# AC.net
KiCad netlist of a schematic drawn in EAGLE
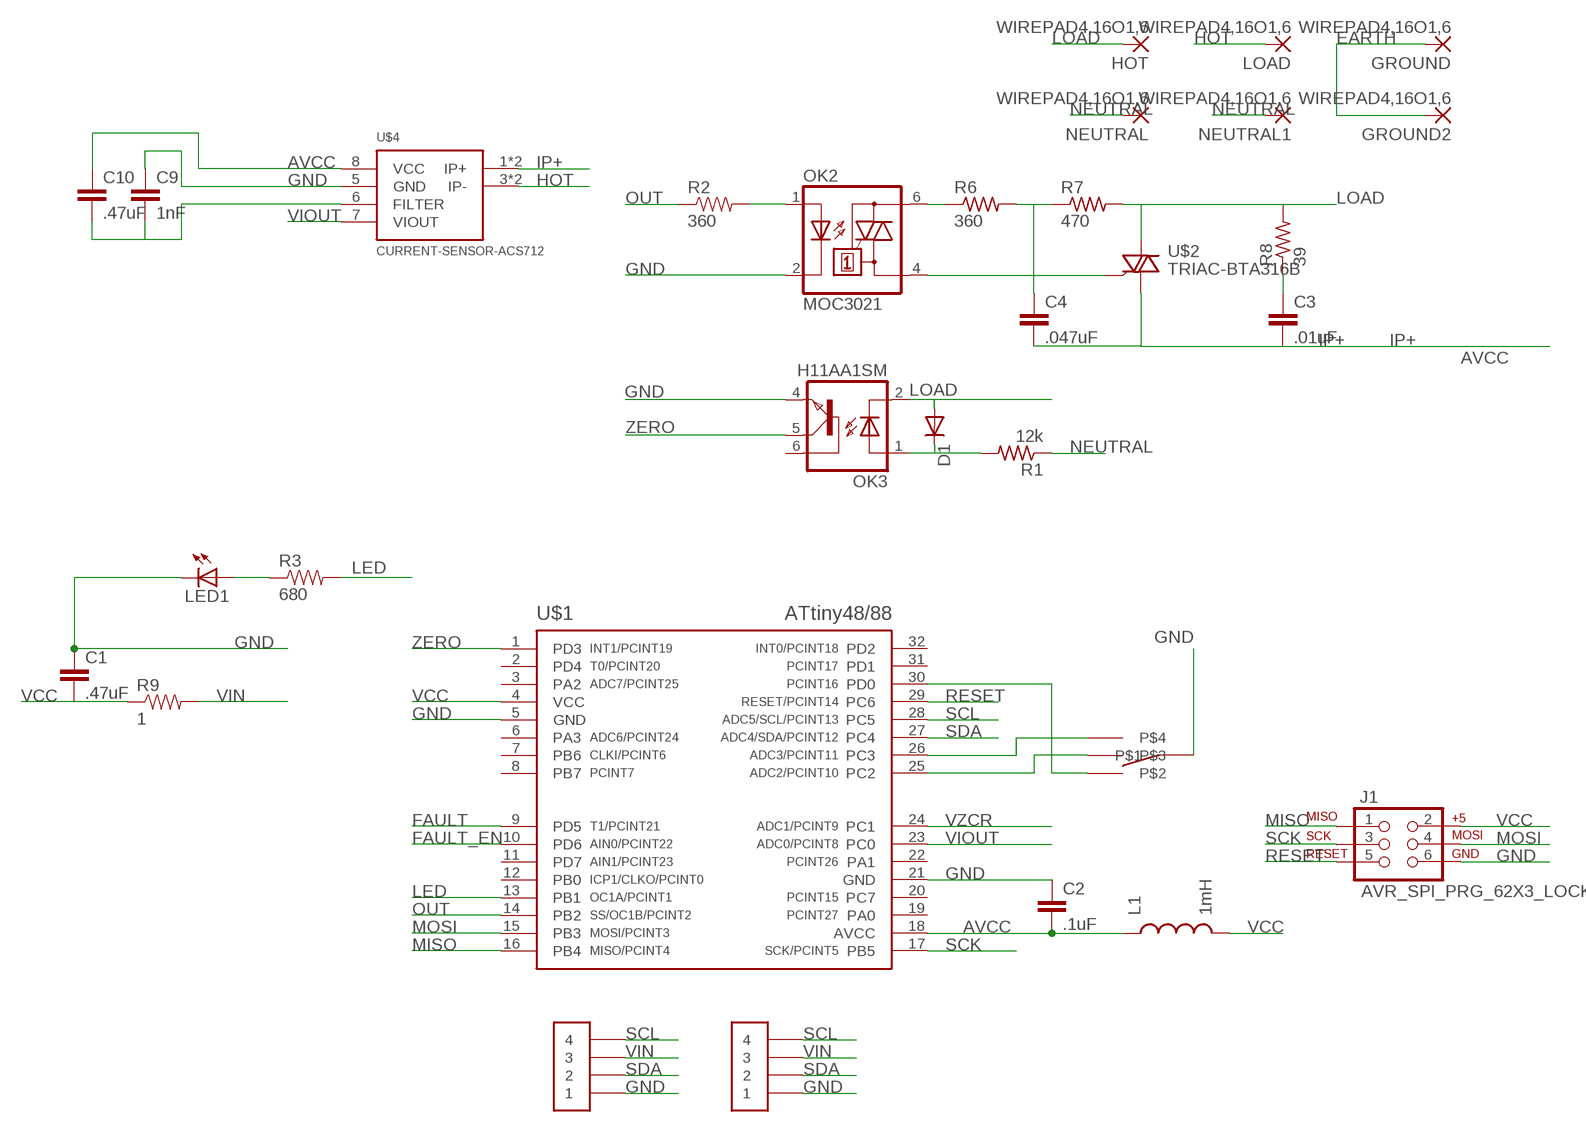
[diagram p0: schematic, sheet 1]

(export (version "E")
  (design (tool "Eeschema 10.0.6"))
  (components
    (comp (ref "C1")
      (value ".47uF")
      (footprint "eagle-import:0805")
      (libsource (lib "eagle-import") (part "CAP0805"))
    )
    (comp (ref "C2")
      (value ".1uF")
      (footprint "eagle-import:0805")
      (libsource (lib "eagle-import") (part "CAP0805"))
    )
    (comp (ref "C3")
      (value ".01uF")
      (footprint "eagle-import:C1206")
      (libsource (lib "eagle-import") (part "C-EUC1206"))
    )
    (comp (ref "C4")
      (value ".047uF")
      (footprint "eagle-import:C1206")
      (libsource (lib "eagle-import") (part "C-EUC1206"))
    )
    (comp (ref "C9")
      (value "1nF")
      (footprint "eagle-import:0805")
      (libsource (lib "eagle-import") (part "CAP0805"))
    )
    (comp (ref "C10")
      (value ".47uF")
      (footprint "eagle-import:0805")
      (libsource (lib "eagle-import") (part "CAP0805"))
    )
    (comp (ref "D1")
      (value "DIODESMA")
      (footprint "eagle-import:SMA-DIODE")
      (libsource (lib "eagle-import") (part "DIODESMA"))
    )
    (comp (ref "GROUND")
      (value "WIREPAD4,16O1,6")
      (footprint "eagle-import:4,16O1,6")
      (libsource (lib "eagle-import") (part "WIREPAD4,16O1,6"))
    )
    (comp (ref "GROUND2")
      (value "WIREPAD4,16O1,6")
      (footprint "eagle-import:4,16O1,6")
      (libsource (lib "eagle-import") (part "WIREPAD4,16O1,6"))
    )
    (comp (ref "HOT")
      (value "WIREPAD4,16O1,6")
      (footprint "eagle-import:4,16O1,6")
      (libsource (lib "eagle-import") (part "WIREPAD4,16O1,6"))
    )
    (comp (ref "J1")
      (value "AVR_SPI_PRG_62X3_LOCK")
      (footprint "eagle-import:2X3_LOCK")
      (libsource (lib "eagle-import") (part "AVR_SPI_PRG_62X3_LOCK"))
    )
    (comp (ref "JP1")
      (value "HEADER-1X4MOLEX-SL")
      (footprint "eagle-import:HEADER-1X4-MOLEX-SL")
      (libsource (lib "eagle-import") (part "HEADER-1X4MOLEX-SL"))
    )
    (comp (ref "JP2")
      (value "HEADER-1X4MOLEX-SL")
      (footprint "eagle-import:HEADER-1X4-MOLEX-SL")
      (libsource (lib "eagle-import") (part "HEADER-1X4MOLEX-SL"))
    )
    (comp (ref "L1")
      (value "1mH")
      (footprint "eagle-import:1007")
      (libsource (lib "eagle-import") (part "INDUCTOR1007"))
    )
    (comp (ref "LED1")
      (value "LED5MM")
      (footprint "eagle-import:LED5MM")
      (libsource (lib "eagle-import") (part "LED5MM"))
    )
    (comp (ref "LOAD")
      (value "WIREPAD4,16O1,6")
      (footprint "eagle-import:4,16O1,6")
      (libsource (lib "eagle-import") (part "WIREPAD4,16O1,6"))
    )
    (comp (ref "NEUTRAL")
      (value "WIREPAD4,16O1,6")
      (footprint "eagle-import:4,16O1,6")
      (libsource (lib "eagle-import") (part "WIREPAD4,16O1,6"))
    )
    (comp (ref "NEUTRAL1")
      (value "WIREPAD4,16O1,6")
      (footprint "eagle-import:4,16O1,6")
      (libsource (lib "eagle-import") (part "WIREPAD4,16O1,6"))
    )
    (comp (ref "OK2")
      (value "MOC3021")
      (footprint "eagle-import:DIL6-SMD")
      (fields (field (name "MF") "FAIRCHILD SEMICONDUCTOR") (field (name "MPN") "MOC3031SM"))
      (libsource (lib "eagle-import") (part "MOC30S31"))
    )
    (comp (ref "OK3")
      (value "H11AA1SM")
      (footprint "eagle-import:DIL6-SMD")
      (libsource (lib "eagle-import") (part "H11A?MS1"))
    )
    (comp (ref "R1")
      (value "12k")
      (footprint "eagle-import:R1206")
      (libsource (lib "eagle-import") (part "R-US_R1206"))
    )
    (comp (ref "R2")
      (value "360")
      (footprint "eagle-import:0805")
      (libsource (lib "eagle-import") (part "SparkFun-Resistors_RESISTOR0805-RES"))
    )
    (comp (ref "R3")
      (value "680")
      (footprint "eagle-import:0805")
      (libsource (lib "eagle-import") (part "RESISTOR0805-RES"))
    )
    (comp (ref "R6")
      (value "360")
      (footprint "eagle-import:R1206")
      (libsource (lib "eagle-import") (part "R-US_R1206"))
    )
    (comp (ref "R7")
      (value "470")
      (footprint "eagle-import:R1206")
      (libsource (lib "eagle-import") (part "R-US_R1206"))
    )
    (comp (ref "R8")
      (value "39")
      (footprint "eagle-import:R1206")
      (libsource (lib "eagle-import") (part "R-US_R1206"))
    )
    (comp (ref "R9")
      (value "1")
      (footprint "eagle-import:0805")
      (libsource (lib "eagle-import") (part "SparkFun-Resistors_RESISTOR0805-RES"))
    )
    (comp (ref "U$1")
      (value "ATTINY48/88-TQFP")
      (footprint "eagle-import:TQFP-32")
      (libsource (lib "eagle-import") (part "ATTINY48/88-TQFP"))
    )
    (comp (ref "U$2")
      (value "TRIAC-BTA316B")
      (footprint "eagle-import:D2PACK")
      (libsource (lib "eagle-import") (part "TRIAC-BTA316B"))
    )
    (comp (ref "U$3")
      (value "SWITCH-SP3T")
      (footprint "eagle-import:SWITCH-SLIDE-APEM-MHS133K")
      (libsource (lib "eagle-import") (part "SWITCH-SP3T"))
    )
    (comp (ref "U$4")
      (value "CURRENT-SENSOR-ACS712")
      (footprint "eagle-import:SOIC-8")
      (libsource (lib "eagle-import") (part "CURRENT-SENSOR-ACS712"))
    )
  )
  (nets
    (net (code "1") (name "/AVCC") (class "Default")
      (node (ref "C10") (pin "1") (pinfunction "1_1") (pintype "passive"))
      (node (ref "C2") (pin "2") (pinfunction "2_2") (pintype "passive"))
      (node (ref "L1") (pin "1") (pinfunction "1_1") (pintype "passive"))
      (node (ref "U$1") (pin "18") (pinfunction "AVCC_18") (pintype "power_in"))
      (node (ref "U$4") (pin "8") (pinfunction "VCC_8") (pintype "bidirectional"))
    )
    (net (code "2") (name "/EARTH") (class "Default")
      (node (ref "GROUND") (pin "1") (pinfunction "P_1") (pintype "passive"))
      (node (ref "GROUND2") (pin "1") (pinfunction "P_1") (pintype "passive"))
    )
    (net (code "3") (name "/FAULT") (class "Default")
      (node (ref "U$1") (pin "9") (pinfunction "PD5_9") (pintype "bidirectional"))
    )
    (net (code "4") (name "/FAULT_EN") (class "Default")
      (node (ref "U$1") (pin "10") (pinfunction "PD6_10") (pintype "bidirectional"))
    )
    (net (code "5") (name "/GND") (class "Default")
      (node (ref "C1") (pin "1") (pinfunction "1_1") (pintype "passive"))
      (node (ref "C2") (pin "1") (pinfunction "1_1") (pintype "passive"))
      (node (ref "C9") (pin "1") (pinfunction "1_1") (pintype "passive"))
      (node (ref "J1") (pin "6") (pinfunction "6_6") (pintype "passive"))
      (node (ref "JP1") (pin "P$1") (pinfunction "1_P$1") (pintype "bidirectional"))
      (node (ref "JP2") (pin "P$1") (pinfunction "1_P$1") (pintype "bidirectional"))
      (node (ref "LED1") (pin "K") (pinfunction "C_K") (pintype "passive"))
      (node (ref "OK2") (pin "2") (pinfunction "C_2") (pintype "passive"))
      (node (ref "OK3") (pin "4") (pinfunction "EMI_4") (pintype "passive"))
      (node (ref "U$1") (pin "21") (pinfunction "GND_21") (pintype "bidirectional"))
      (node (ref "U$1") (pin "5") (pinfunction "GND_5") (pintype "bidirectional"))
      (node (ref "U$3") (pin "P2") (pinfunction "P$1_P2") (pintype "bidirectional"))
      (node (ref "U$4") (pin "5") (pinfunction "GND_5") (pintype "bidirectional"))
    )
    (net (code "6") (name "/HOT") (class "Default")
      (node (ref "LOAD") (pin "1") (pinfunction "P_1") (pintype "passive"))
      (node (ref "U$4") (pin "3") (pinfunction "IP-_3") (pintype "bidirectional"))
      (node (ref "U$4") (pin "4") (pinfunction "IP-_4") (pintype "bidirectional"))
    )
    (net (code "7") (name "/IP+") (class "Default")
      (node (ref "C3") (pin "2") (pinfunction "2_2") (pintype "passive"))
      (node (ref "C4") (pin "2") (pinfunction "2_2") (pintype "passive"))
      (node (ref "U$2") (pin "1") (pinfunction "A1_1") (pintype "passive"))
      (node (ref "U$4") (pin "1") (pinfunction "IP+_1") (pintype "bidirectional"))
      (node (ref "U$4") (pin "2") (pinfunction "IP+_2") (pintype "bidirectional"))
    )
    (net (code "8") (name "/LED") (class "Default")
      (node (ref "R3") (pin "2") (pinfunction "2_2") (pintype "passive"))
      (node (ref "U$1") (pin "13") (pinfunction "PB1_13") (pintype "bidirectional"))
    )
    (net (code "9") (name "/LOAD") (class "Default")
      (node (ref "D1") (pin "A") (pinfunction "A_A") (pintype "passive"))
      (node (ref "HOT") (pin "1") (pinfunction "P_1") (pintype "passive"))
      (node (ref "OK3") (pin "2") (pinfunction "C_2") (pintype "passive"))
      (node (ref "R7") (pin "2") (pinfunction "2_2") (pintype "passive"))
      (node (ref "R8") (pin "2") (pinfunction "2_2") (pintype "passive"))
      (node (ref "U$2") (pin "2") (pinfunction "A2_2") (pintype "passive"))
    )
    (net (code "10") (name "/MISO") (class "Default")
      (node (ref "J1") (pin "1") (pinfunction "1_1") (pintype "passive"))
      (node (ref "U$1") (pin "16") (pinfunction "PB4_16") (pintype "bidirectional"))
    )
    (net (code "11") (name "/MOSI") (class "Default")
      (node (ref "J1") (pin "4") (pinfunction "4_4") (pintype "passive"))
      (node (ref "U$1") (pin "15") (pinfunction "PB3_15") (pintype "bidirectional"))
    )
    (net (code "12") (name "/NEUTRAL") (class "Default")
      (node (ref "NEUTRAL") (pin "1") (pinfunction "P_1") (pintype "passive"))
      (node (ref "NEUTRAL1") (pin "1") (pinfunction "P_1") (pintype "passive"))
      (node (ref "R1") (pin "1") (pinfunction "1_1") (pintype "passive"))
    )
    (net (code "13") (name "/OUT") (class "Default")
      (node (ref "R2") (pin "1") (pinfunction "1_1") (pintype "passive"))
      (node (ref "U$1") (pin "14") (pinfunction "PB2_14") (pintype "bidirectional"))
    )
    (net (code "14") (name "/RESET") (class "Default")
      (node (ref "J1") (pin "5") (pinfunction "5_5") (pintype "passive"))
      (node (ref "U$1") (pin "29") (pinfunction "PC6_29") (pintype "bidirectional"))
    )
    (net (code "15") (name "/SCK") (class "Default")
      (node (ref "J1") (pin "3") (pinfunction "3_3") (pintype "passive"))
      (node (ref "U$1") (pin "17") (pinfunction "PB5_17") (pintype "bidirectional"))
    )
    (net (code "16") (name "/SCL") (class "Default")
      (node (ref "JP1") (pin "P$4") (pinfunction "4_P$4") (pintype "bidirectional"))
      (node (ref "JP2") (pin "P$4") (pinfunction "4_P$4") (pintype "bidirectional"))
      (node (ref "U$1") (pin "28") (pinfunction "PC5_28") (pintype "bidirectional"))
    )
    (net (code "17") (name "/SDA") (class "Default")
      (node (ref "JP1") (pin "P$2") (pinfunction "2_P$2") (pintype "bidirectional"))
      (node (ref "JP2") (pin "P$2") (pinfunction "2_P$2") (pintype "bidirectional"))
      (node (ref "U$1") (pin "27") (pinfunction "PC4_27") (pintype "bidirectional"))
    )
    (net (code "18") (name "/VCC") (class "Default")
      (node (ref "C1") (pin "2") (pinfunction "2_2") (pintype "passive"))
      (node (ref "J1") (pin "2") (pinfunction "2_2") (pintype "passive"))
      (node (ref "L1") (pin "2") (pinfunction "2_2") (pintype "passive"))
      (node (ref "R9") (pin "1") (pinfunction "1_1") (pintype "passive"))
      (node (ref "U$1") (pin "4") (pinfunction "VCC_4") (pintype "bidirectional"))
    )
    (net (code "19") (name "/VIN") (class "Default")
      (node (ref "JP1") (pin "P$3") (pinfunction "3_P$3") (pintype "bidirectional"))
      (node (ref "JP2") (pin "P$3") (pinfunction "3_P$3") (pintype "bidirectional"))
      (node (ref "R9") (pin "2") (pinfunction "2_2") (pintype "passive"))
    )
    (net (code "20") (name "/VIOUT") (class "Default")
      (node (ref "U$1") (pin "23") (pinfunction "PC0_23") (pintype "bidirectional"))
      (node (ref "U$4") (pin "7") (pinfunction "VIOUT_7") (pintype "bidirectional"))
    )
    (net (code "21") (name "/VZCR") (class "Default")
      (node (ref "U$1") (pin "24") (pinfunction "PC1_24") (pintype "bidirectional"))
    )
    (net (code "22") (name "/ZERO") (class "Default")
      (node (ref "OK3") (pin "5") (pinfunction "COL_5") (pintype "passive"))
      (node (ref "U$1") (pin "1") (pinfunction "PD3_1") (pintype "bidirectional"))
    )
    (net (code "23") (name "Net-(C3-Pad1)") (class "Default")
      (node (ref "C3") (pin "1") (pinfunction "1_1") (pintype "passive"))
      (node (ref "R8") (pin "1") (pinfunction "1_1") (pintype "passive"))
    )
    (net (code "24") (name "Net-(C4-Pad1)") (class "Default")
      (node (ref "C4") (pin "1") (pinfunction "1_1") (pintype "passive"))
      (node (ref "R6") (pin "2") (pinfunction "2_2") (pintype "passive"))
      (node (ref "R7") (pin "1") (pinfunction "1_1") (pintype "passive"))
    )
    (net (code "25") (name "Net-(LED1-PadA)") (class "Default")
      (node (ref "LED1") (pin "A") (pinfunction "A_A") (pintype "passive"))
      (node (ref "R3") (pin "1") (pinfunction "1_1") (pintype "passive"))
    )
    (net (code "26") (name "Net-(OK2-A)") (class "Default")
      (node (ref "OK2") (pin "1") (pinfunction "A_1") (pintype "passive"))
      (node (ref "R2") (pin "2") (pinfunction "2_2") (pintype "passive"))
    )
    (net (code "27") (name "Net-(OK2-A1)") (class "Default")
      (node (ref "OK2") (pin "4") (pinfunction "A1_4") (pintype "passive"))
      (node (ref "U$2") (pin "3") (pinfunction "G_3") (pintype "passive"))
    )
    (net (code "28") (name "Net-(OK2-A2)") (class "Default")
      (node (ref "OK2") (pin "6") (pinfunction "A2_6") (pintype "passive"))
      (node (ref "R6") (pin "1") (pinfunction "1_1") (pintype "passive"))
    )
    (net (code "29") (name "Net-(OK3-A)") (class "Default")
      (node (ref "D1") (pin "C") (pinfunction "C_C") (pintype "passive"))
      (node (ref "OK3") (pin "1") (pinfunction "A_1") (pintype "passive"))
      (node (ref "R1") (pin "2") (pinfunction "2_2") (pintype "passive"))
    )
    (net (code "30") (name "Net-(U$1-PC2)") (class "Default")
      (node (ref "U$1") (pin "25") (pinfunction "PC2_25") (pintype "bidirectional"))
      (node (ref "U$3") (pin "P3") (pinfunction "P$3_P3") (pintype "bidirectional"))
    )
    (net (code "31") (name "Net-(U$1-PC3)") (class "Default")
      (node (ref "U$1") (pin "26") (pinfunction "PC3_26") (pintype "bidirectional"))
      (node (ref "U$3") (pin "P4") (pinfunction "P$4_P4") (pintype "bidirectional"))
    )
    (net (code "32") (name "Net-(U$1-PD0)") (class "Default")
      (node (ref "U$1") (pin "30") (pinfunction "PD0_30") (pintype "bidirectional"))
      (node (ref "U$3") (pin "P1") (pinfunction "P$2_P1") (pintype "bidirectional"))
    )
    (net (code "33") (name "Net-(U$4-FILTER)") (class "Default")
      (node (ref "C10") (pin "2") (pinfunction "2_2") (pintype "passive"))
      (node (ref "C9") (pin "2") (pinfunction "2_2") (pintype "passive"))
      (node (ref "U$4") (pin "6") (pinfunction "FILTER_6") (pintype "bidirectional"))
    )
    (net (code "34") (name "unconnected-(OK3-BAS-Pad6)") (class "Default")
      (node (ref "OK3") (pin "6") (pinfunction "BAS_6") (pintype "passive"))
    )
    (net (code "35") (name "unconnected-(U$1-PA0-Pad19)") (class "Default")
      (node (ref "U$1") (pin "19") (pinfunction "PA0_19") (pintype "bidirectional"))
    )
    (net (code "36") (name "unconnected-(U$1-PA1-Pad22)") (class "Default")
      (node (ref "U$1") (pin "22") (pinfunction "PA1_22") (pintype "bidirectional"))
    )
    (net (code "37") (name "unconnected-(U$1-PA2-Pad3)") (class "Default")
      (node (ref "U$1") (pin "3") (pinfunction "PA2_3") (pintype "bidirectional"))
    )
    (net (code "38") (name "unconnected-(U$1-PA3-Pad6)") (class "Default")
      (node (ref "U$1") (pin "6") (pinfunction "PA3_6") (pintype "bidirectional"))
    )
    (net (code "39") (name "unconnected-(U$1-PB0-Pad12)") (class "Default")
      (node (ref "U$1") (pin "12") (pinfunction "PB0_12") (pintype "bidirectional"))
    )
    (net (code "40") (name "unconnected-(U$1-PB6-Pad7)") (class "Default")
      (node (ref "U$1") (pin "7") (pinfunction "PB6_7") (pintype "bidirectional"))
    )
    (net (code "41") (name "unconnected-(U$1-PB7-Pad8)") (class "Default")
      (node (ref "U$1") (pin "8") (pinfunction "PB7_8") (pintype "bidirectional"))
    )
    (net (code "42") (name "unconnected-(U$1-PC7-Pad20)") (class "Default")
      (node (ref "U$1") (pin "20") (pinfunction "PC7_20") (pintype "bidirectional"))
    )
    (net (code "43") (name "unconnected-(U$1-PD1-Pad31)") (class "Default")
      (node (ref "U$1") (pin "31") (pinfunction "PD1_31") (pintype "bidirectional"))
    )
    (net (code "44") (name "unconnected-(U$1-PD2-Pad32)") (class "Default")
      (node (ref "U$1") (pin "32") (pinfunction "PD2_32") (pintype "bidirectional"))
    )
    (net (code "45") (name "unconnected-(U$1-PD4-Pad2)") (class "Default")
      (node (ref "U$1") (pin "2") (pinfunction "PD4_2") (pintype "bidirectional"))
    )
    (net (code "46") (name "unconnected-(U$1-PD7-Pad11)") (class "Default")
      (node (ref "U$1") (pin "11") (pinfunction "PD7_11") (pintype "bidirectional"))
    )
  )
)
